# SCH_ALL-IN-ONE_2025-01-04.net
KiCad netlist of a schematic drawn in EasyEDA
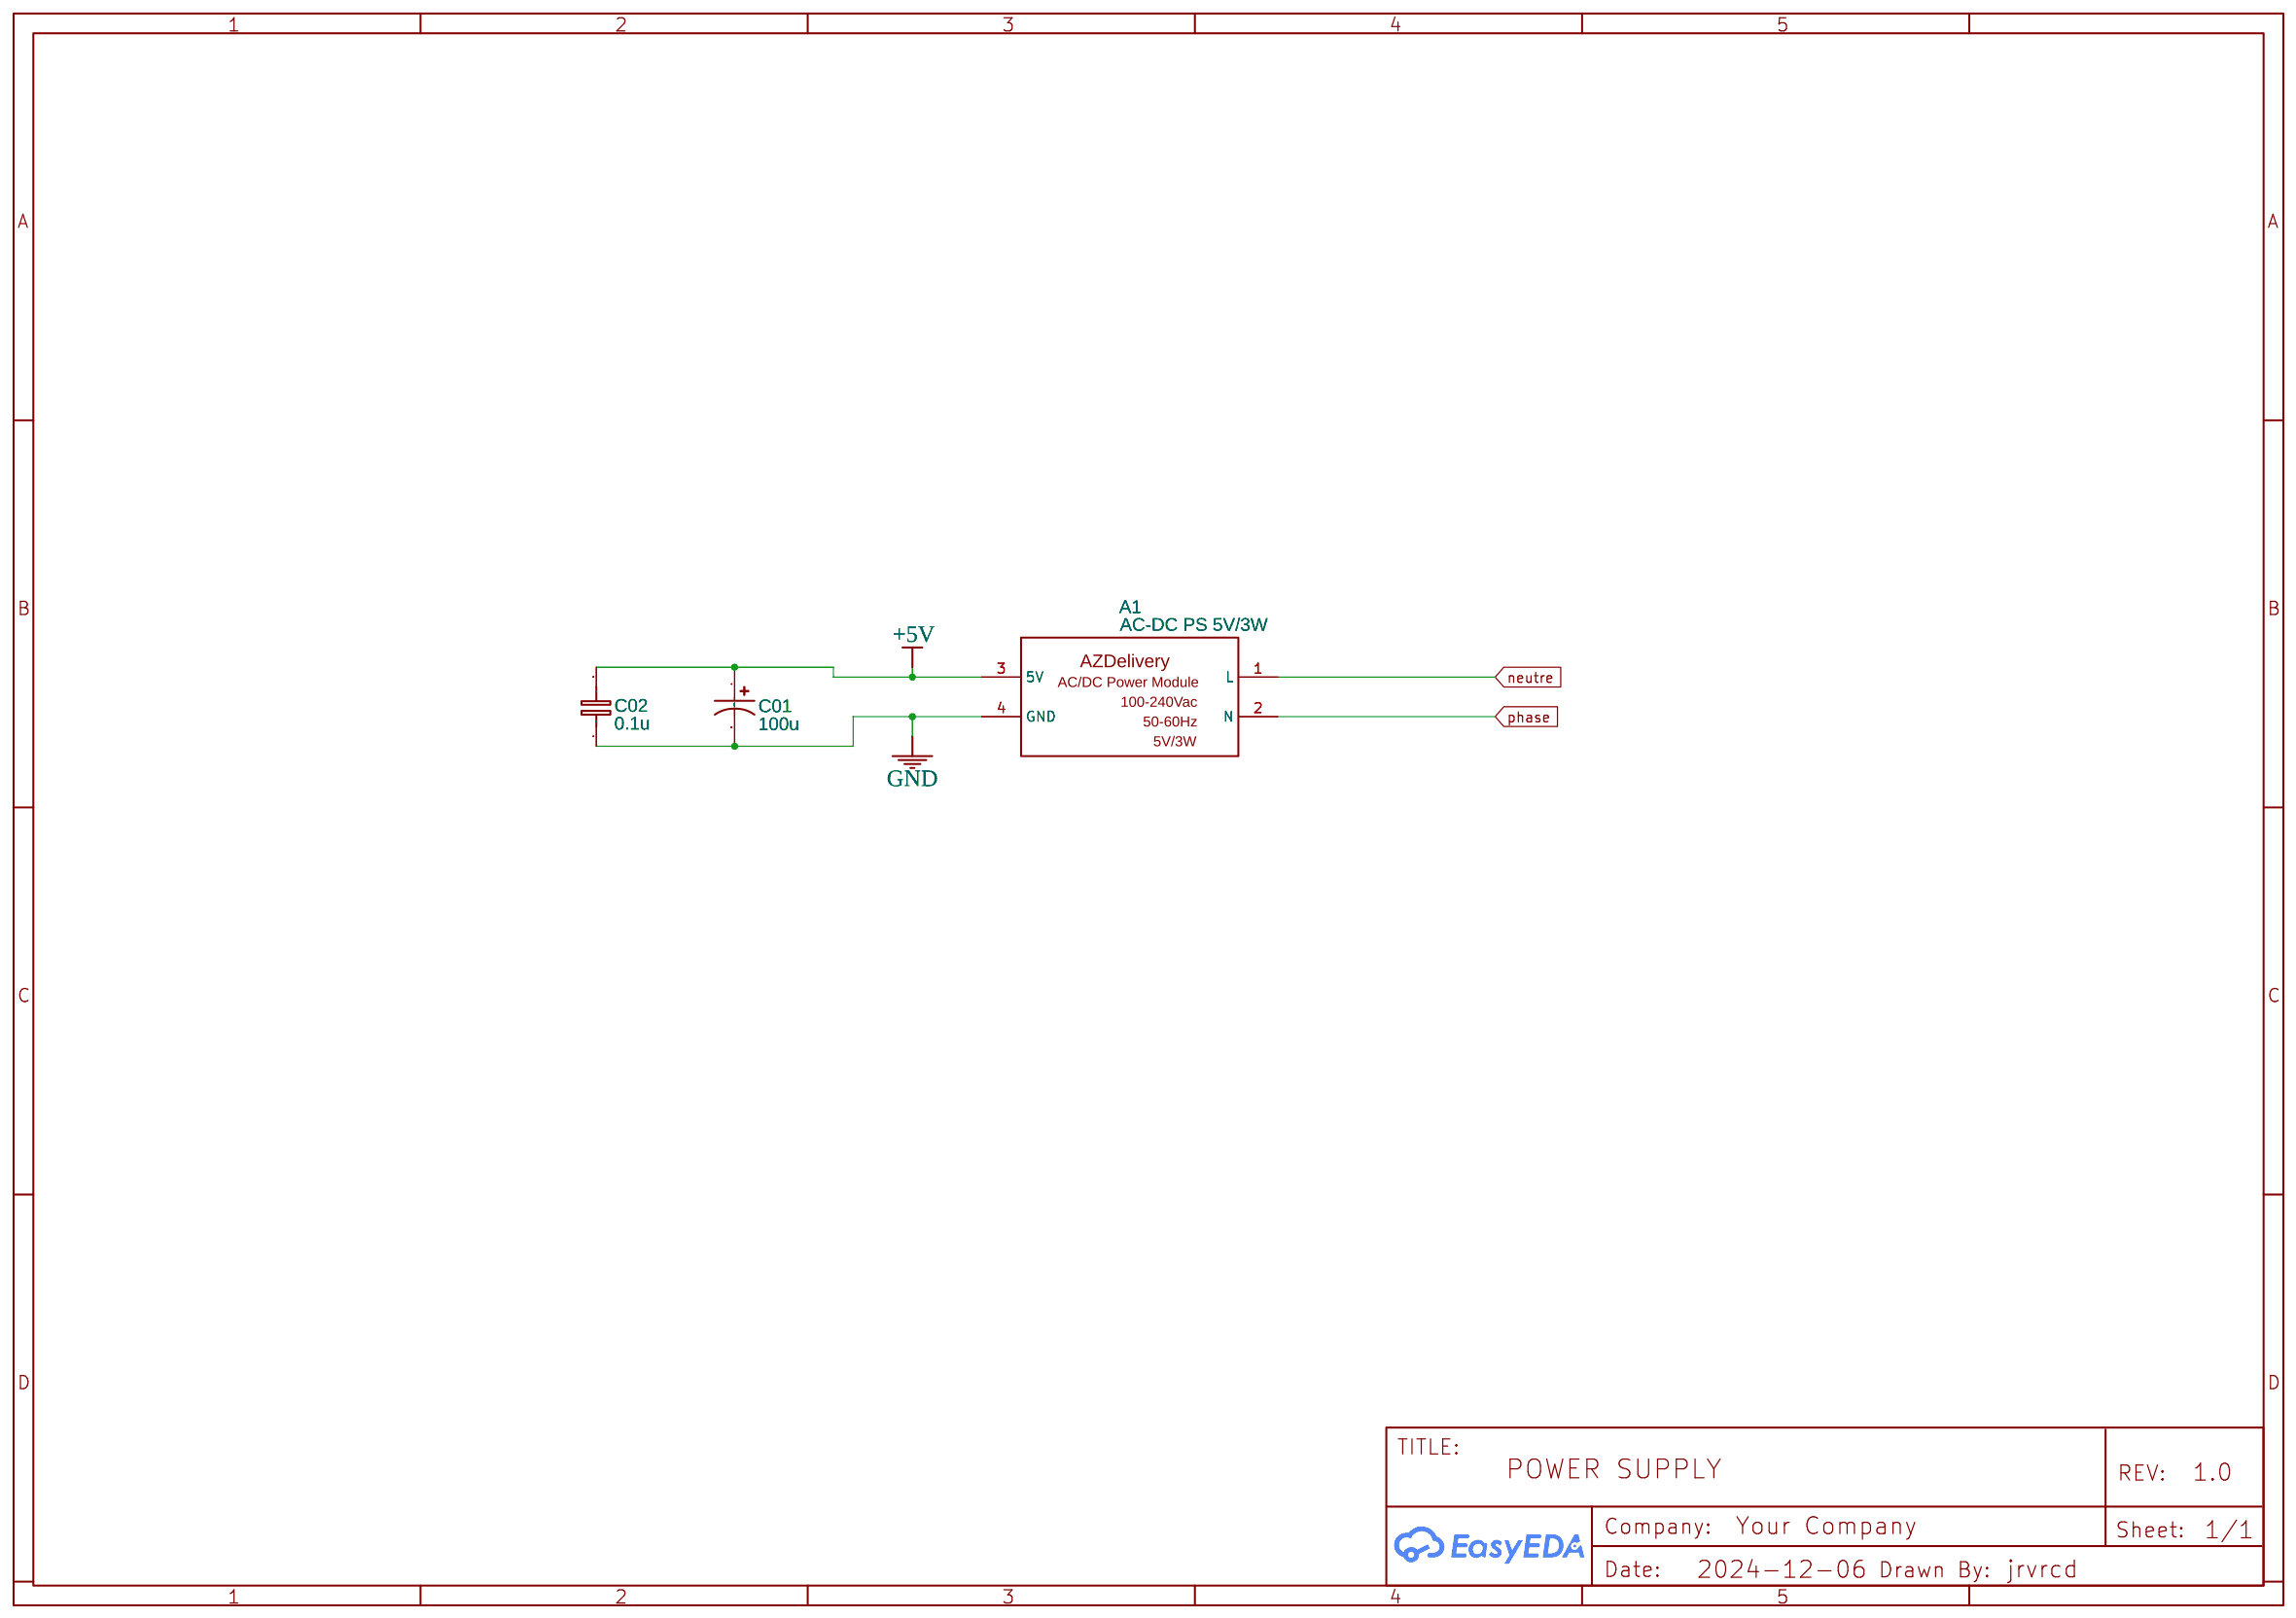
[diagram p0: power supply]
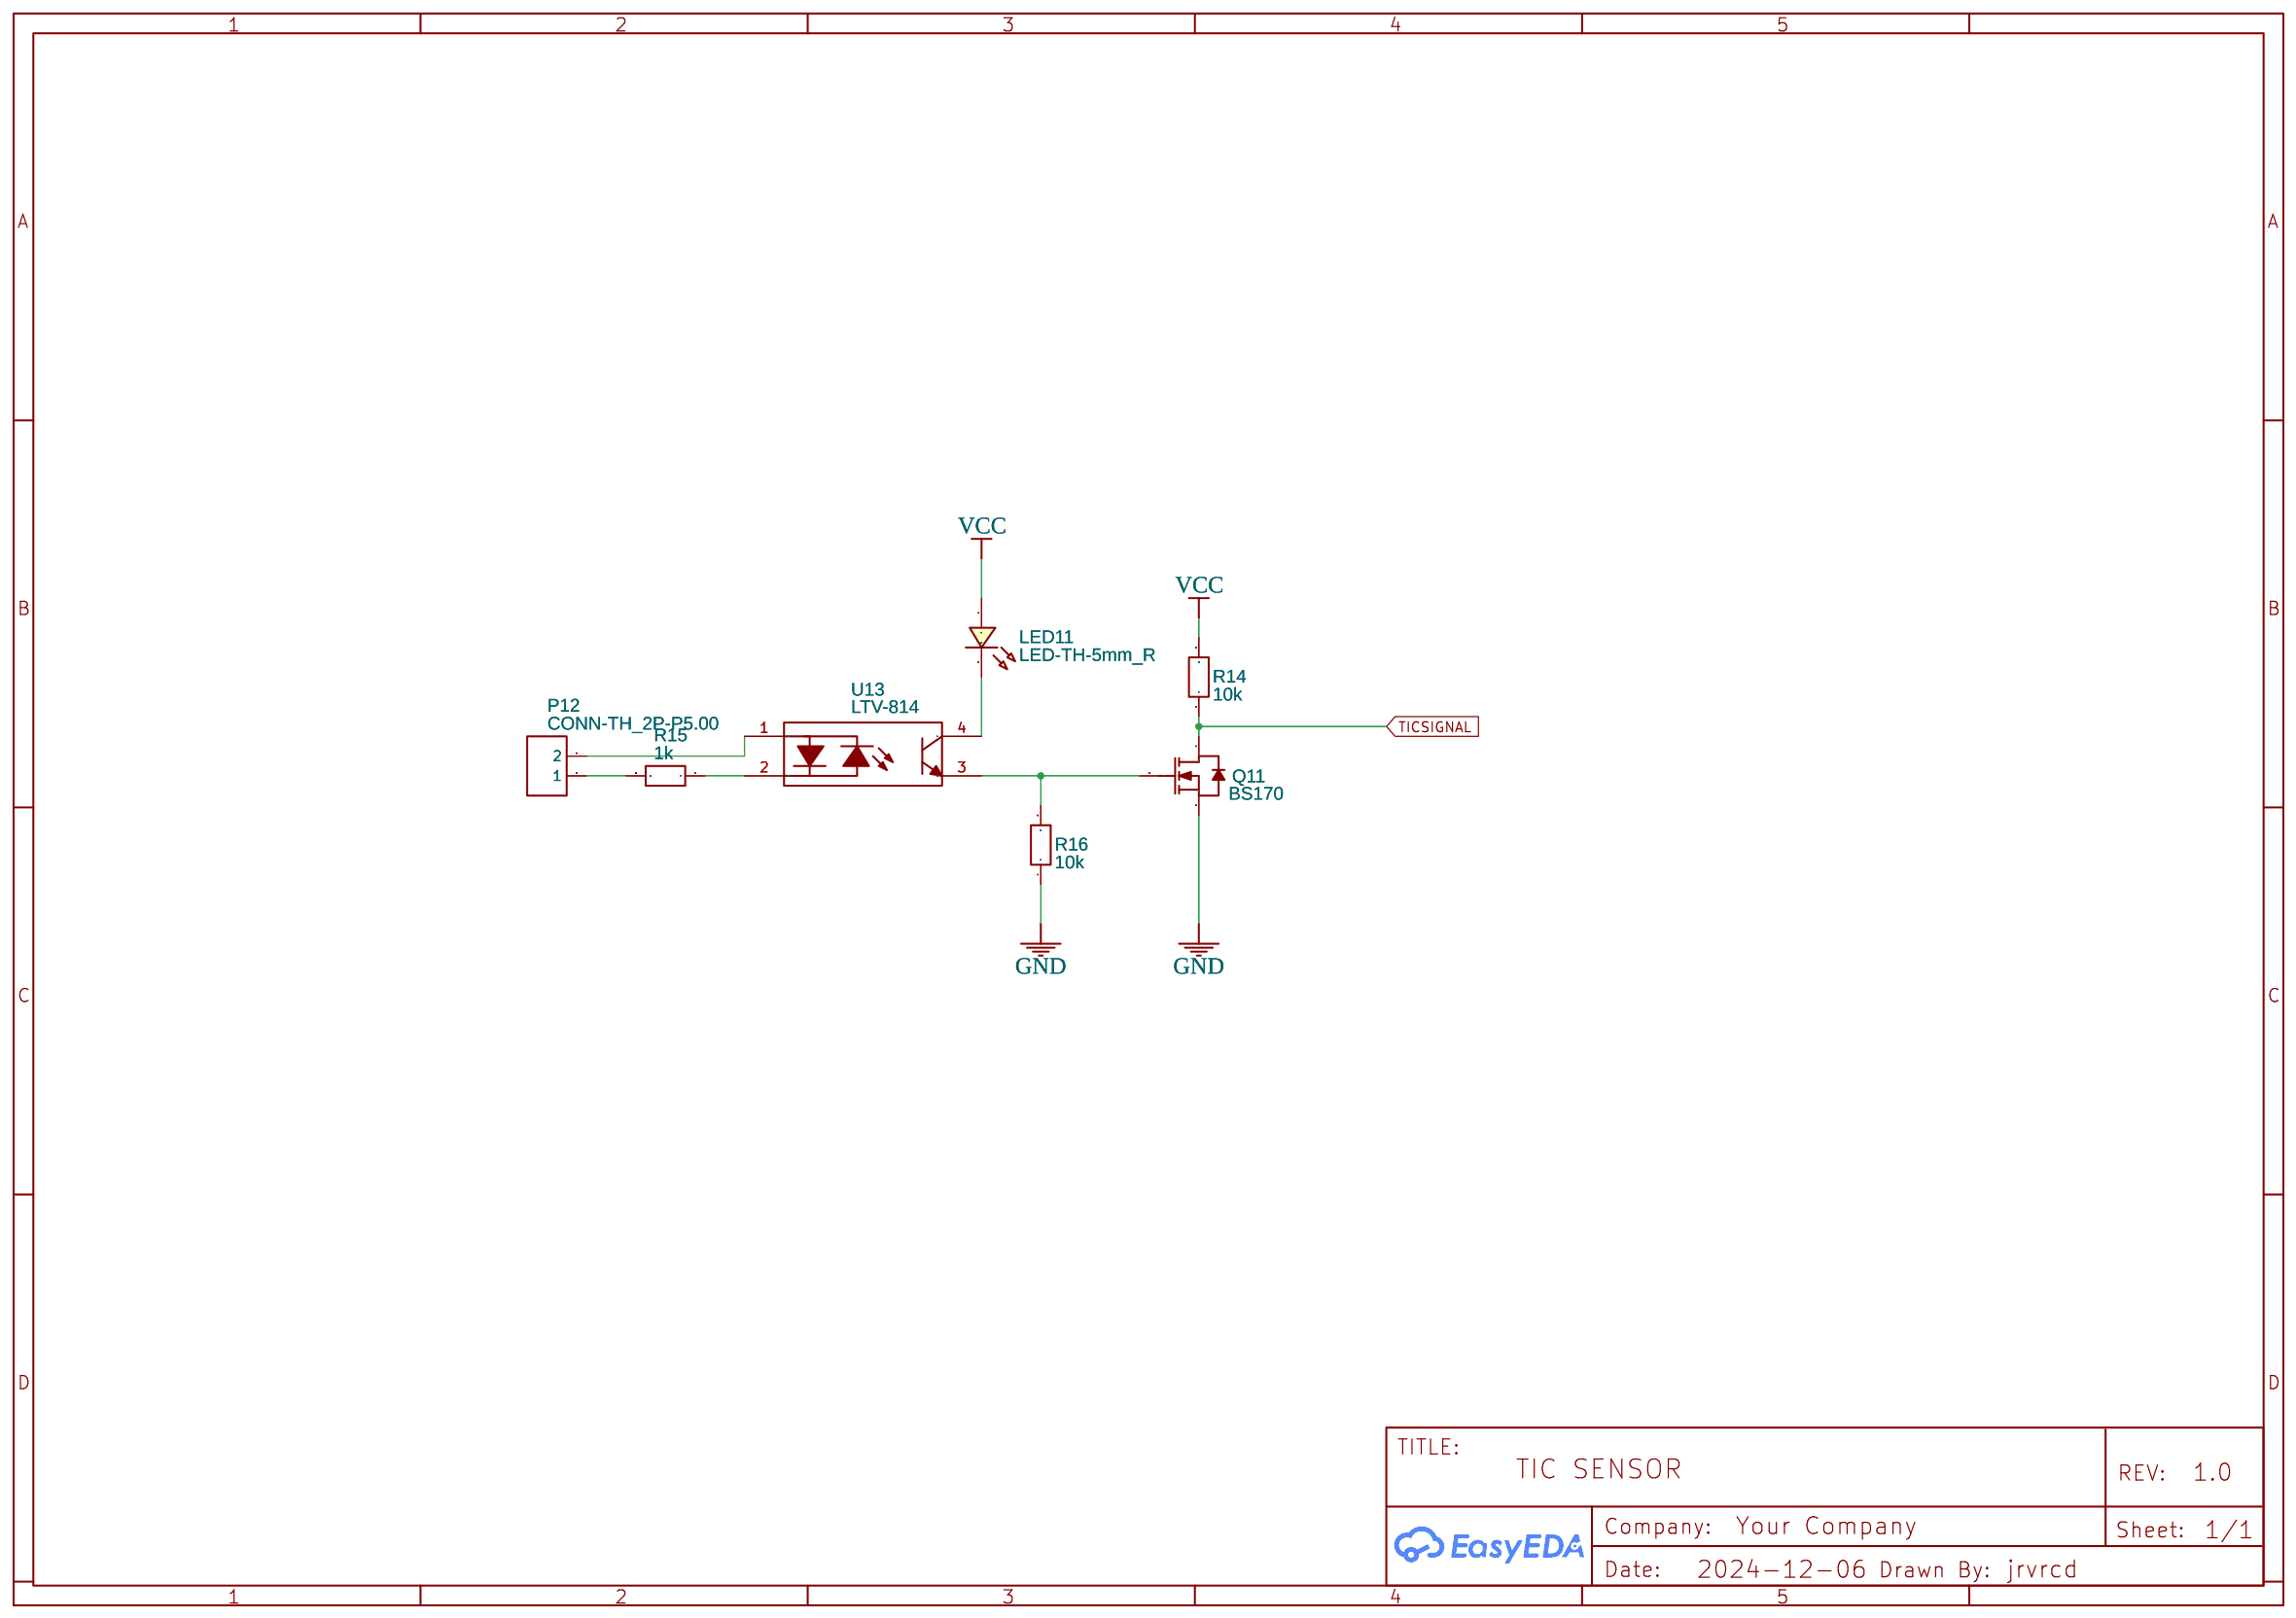
[diagram p1: TIC SENSOR]
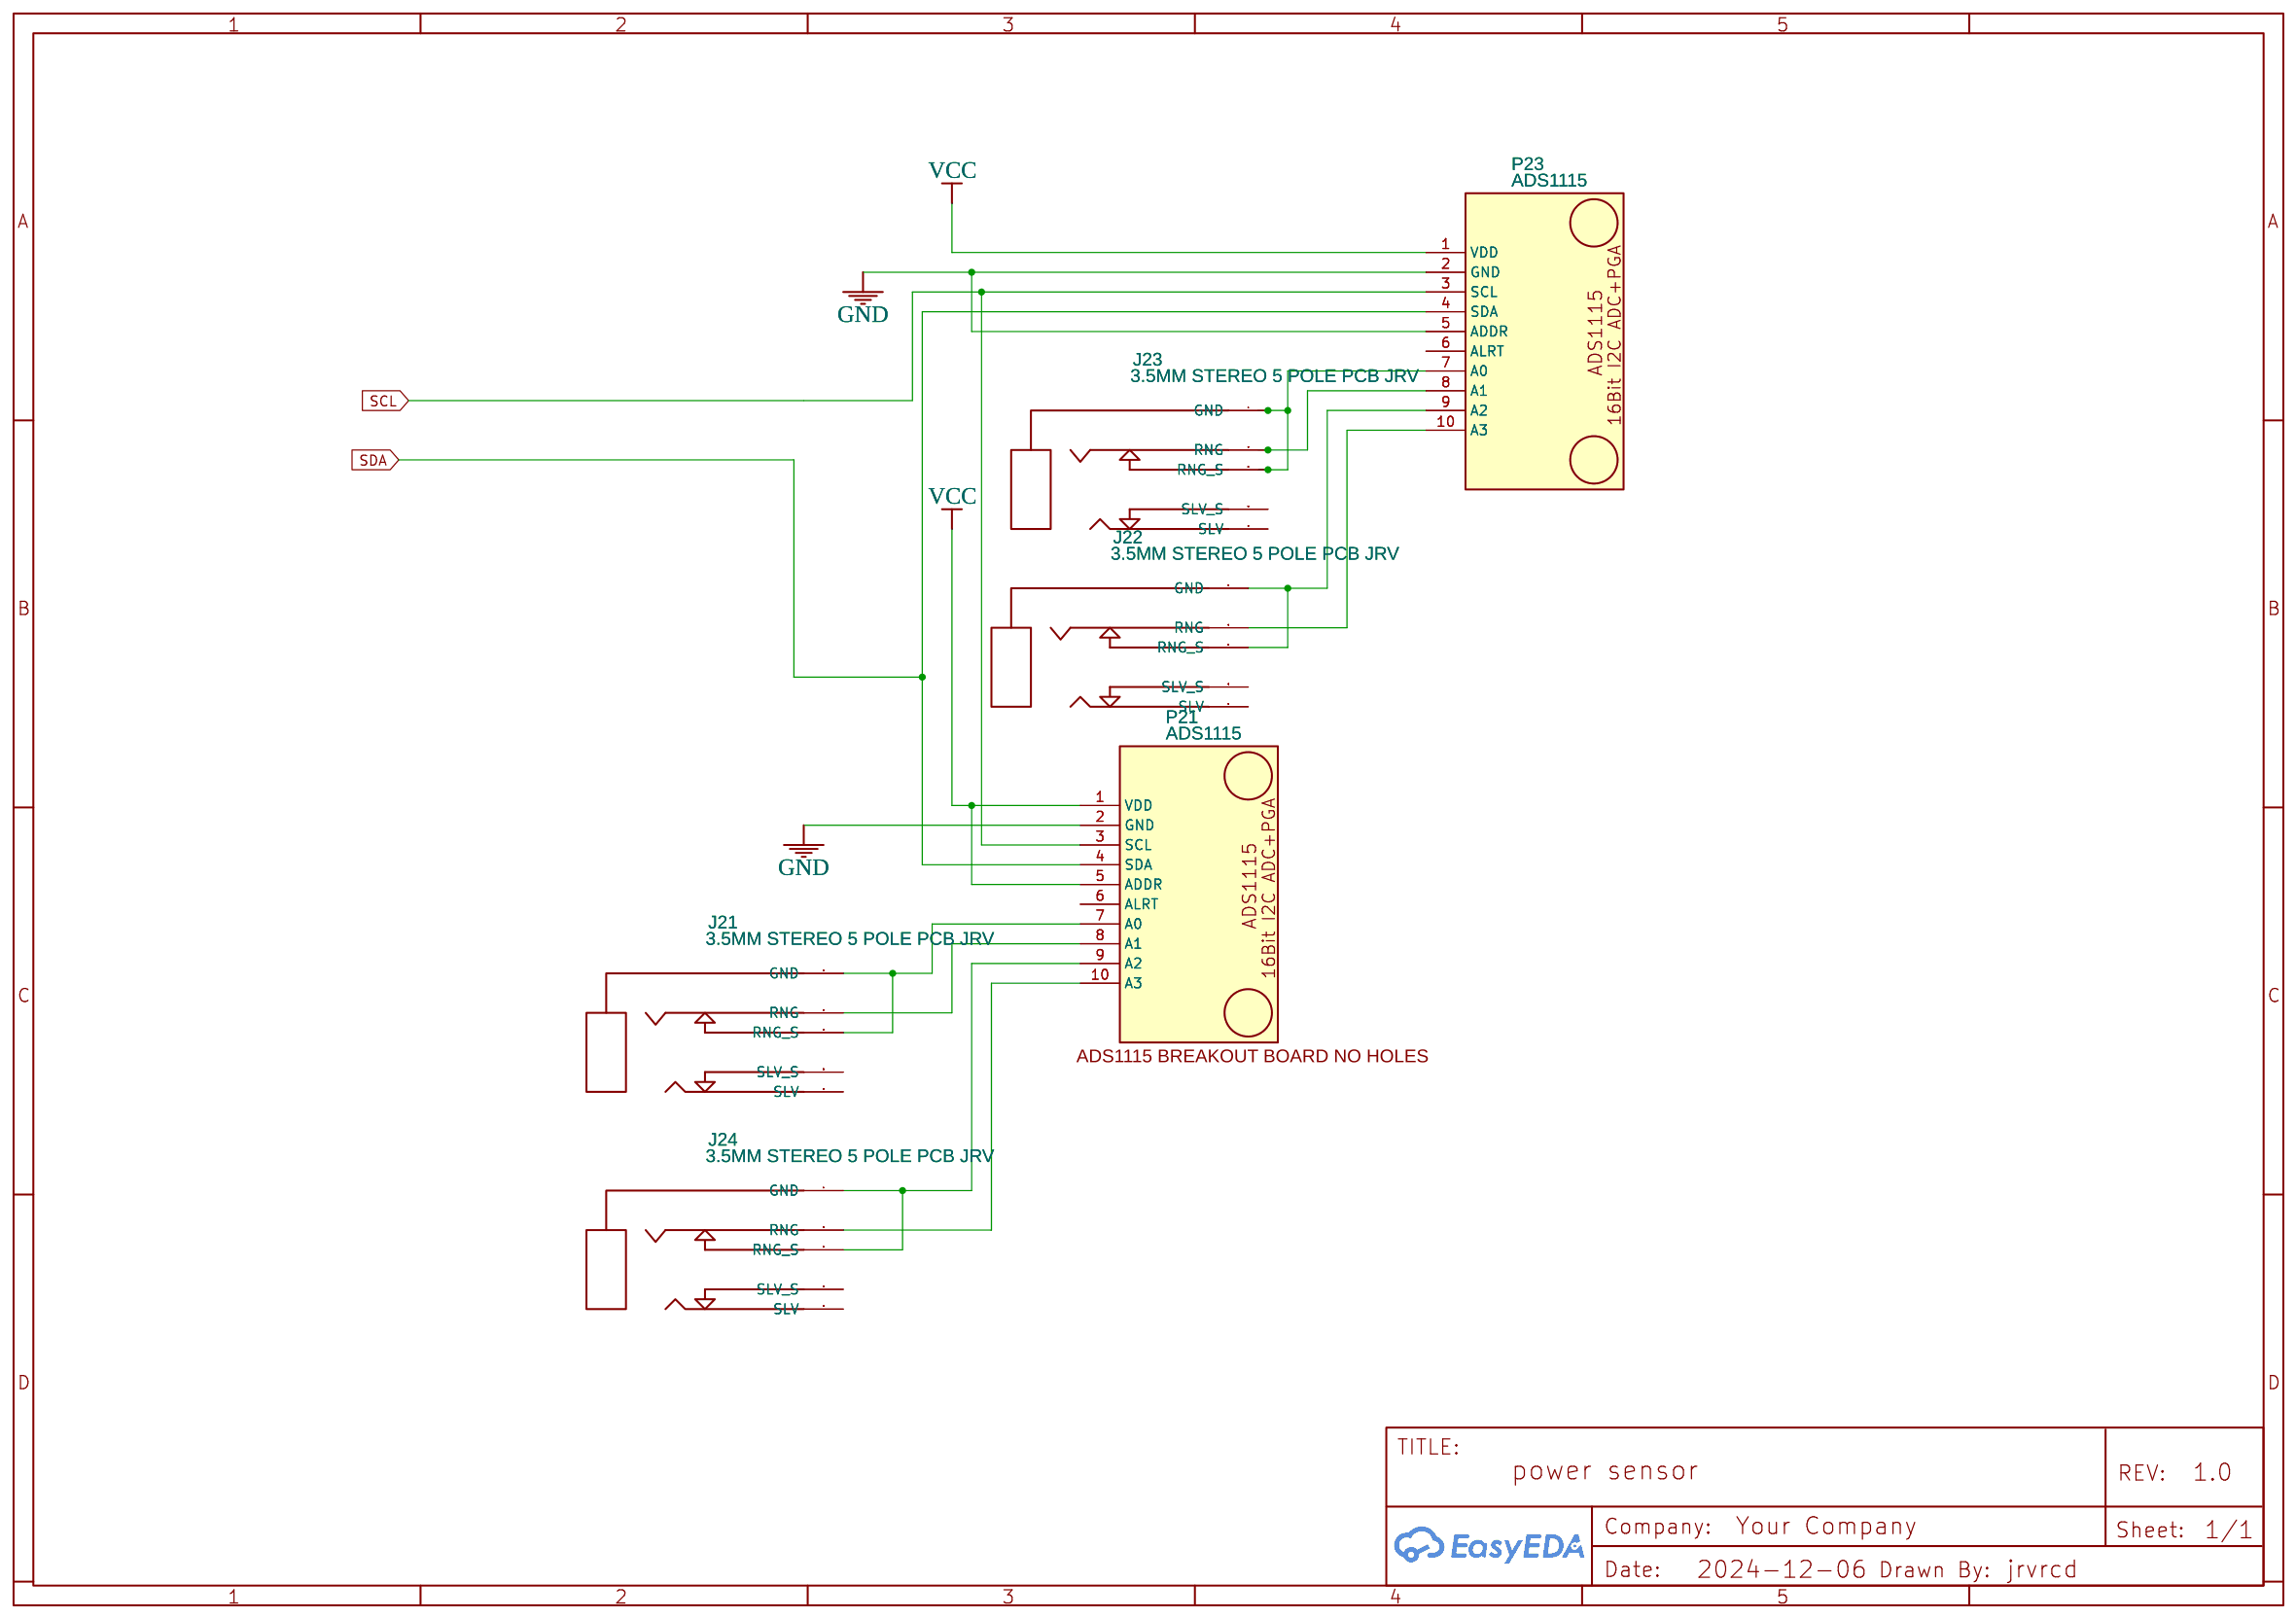
[diagram p2: POWER SENSOR]
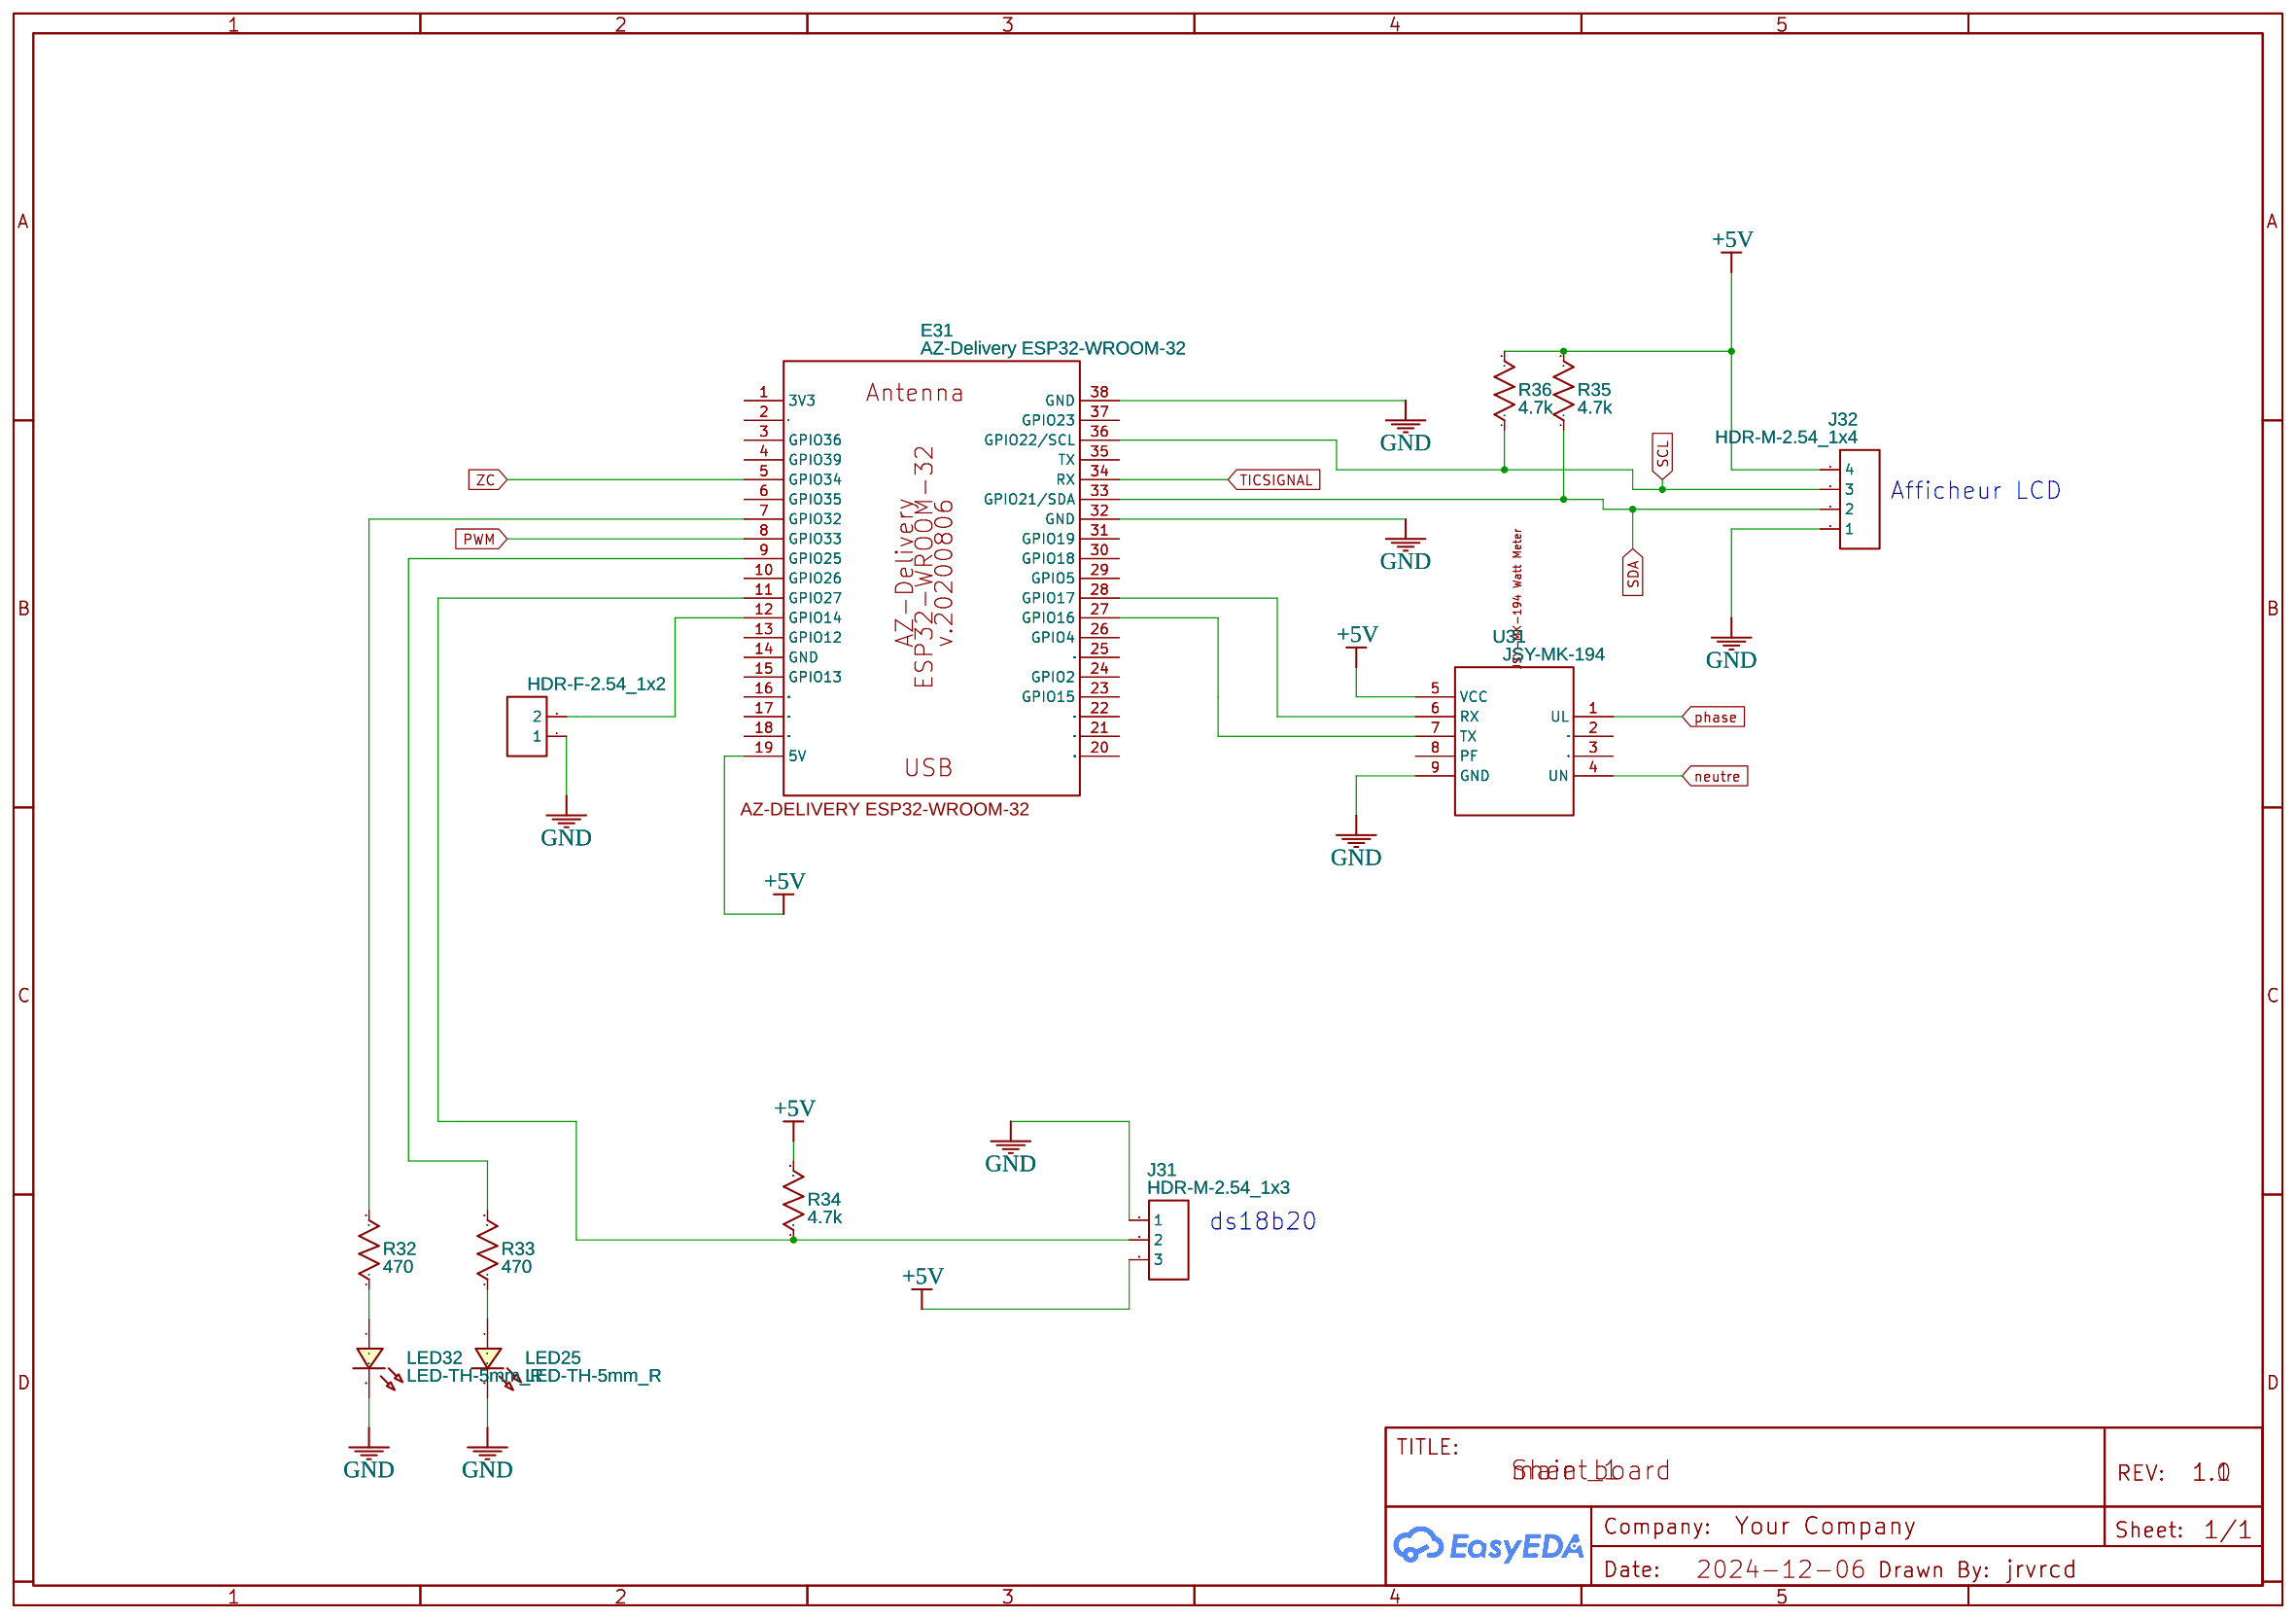
[diagram p3: main board]
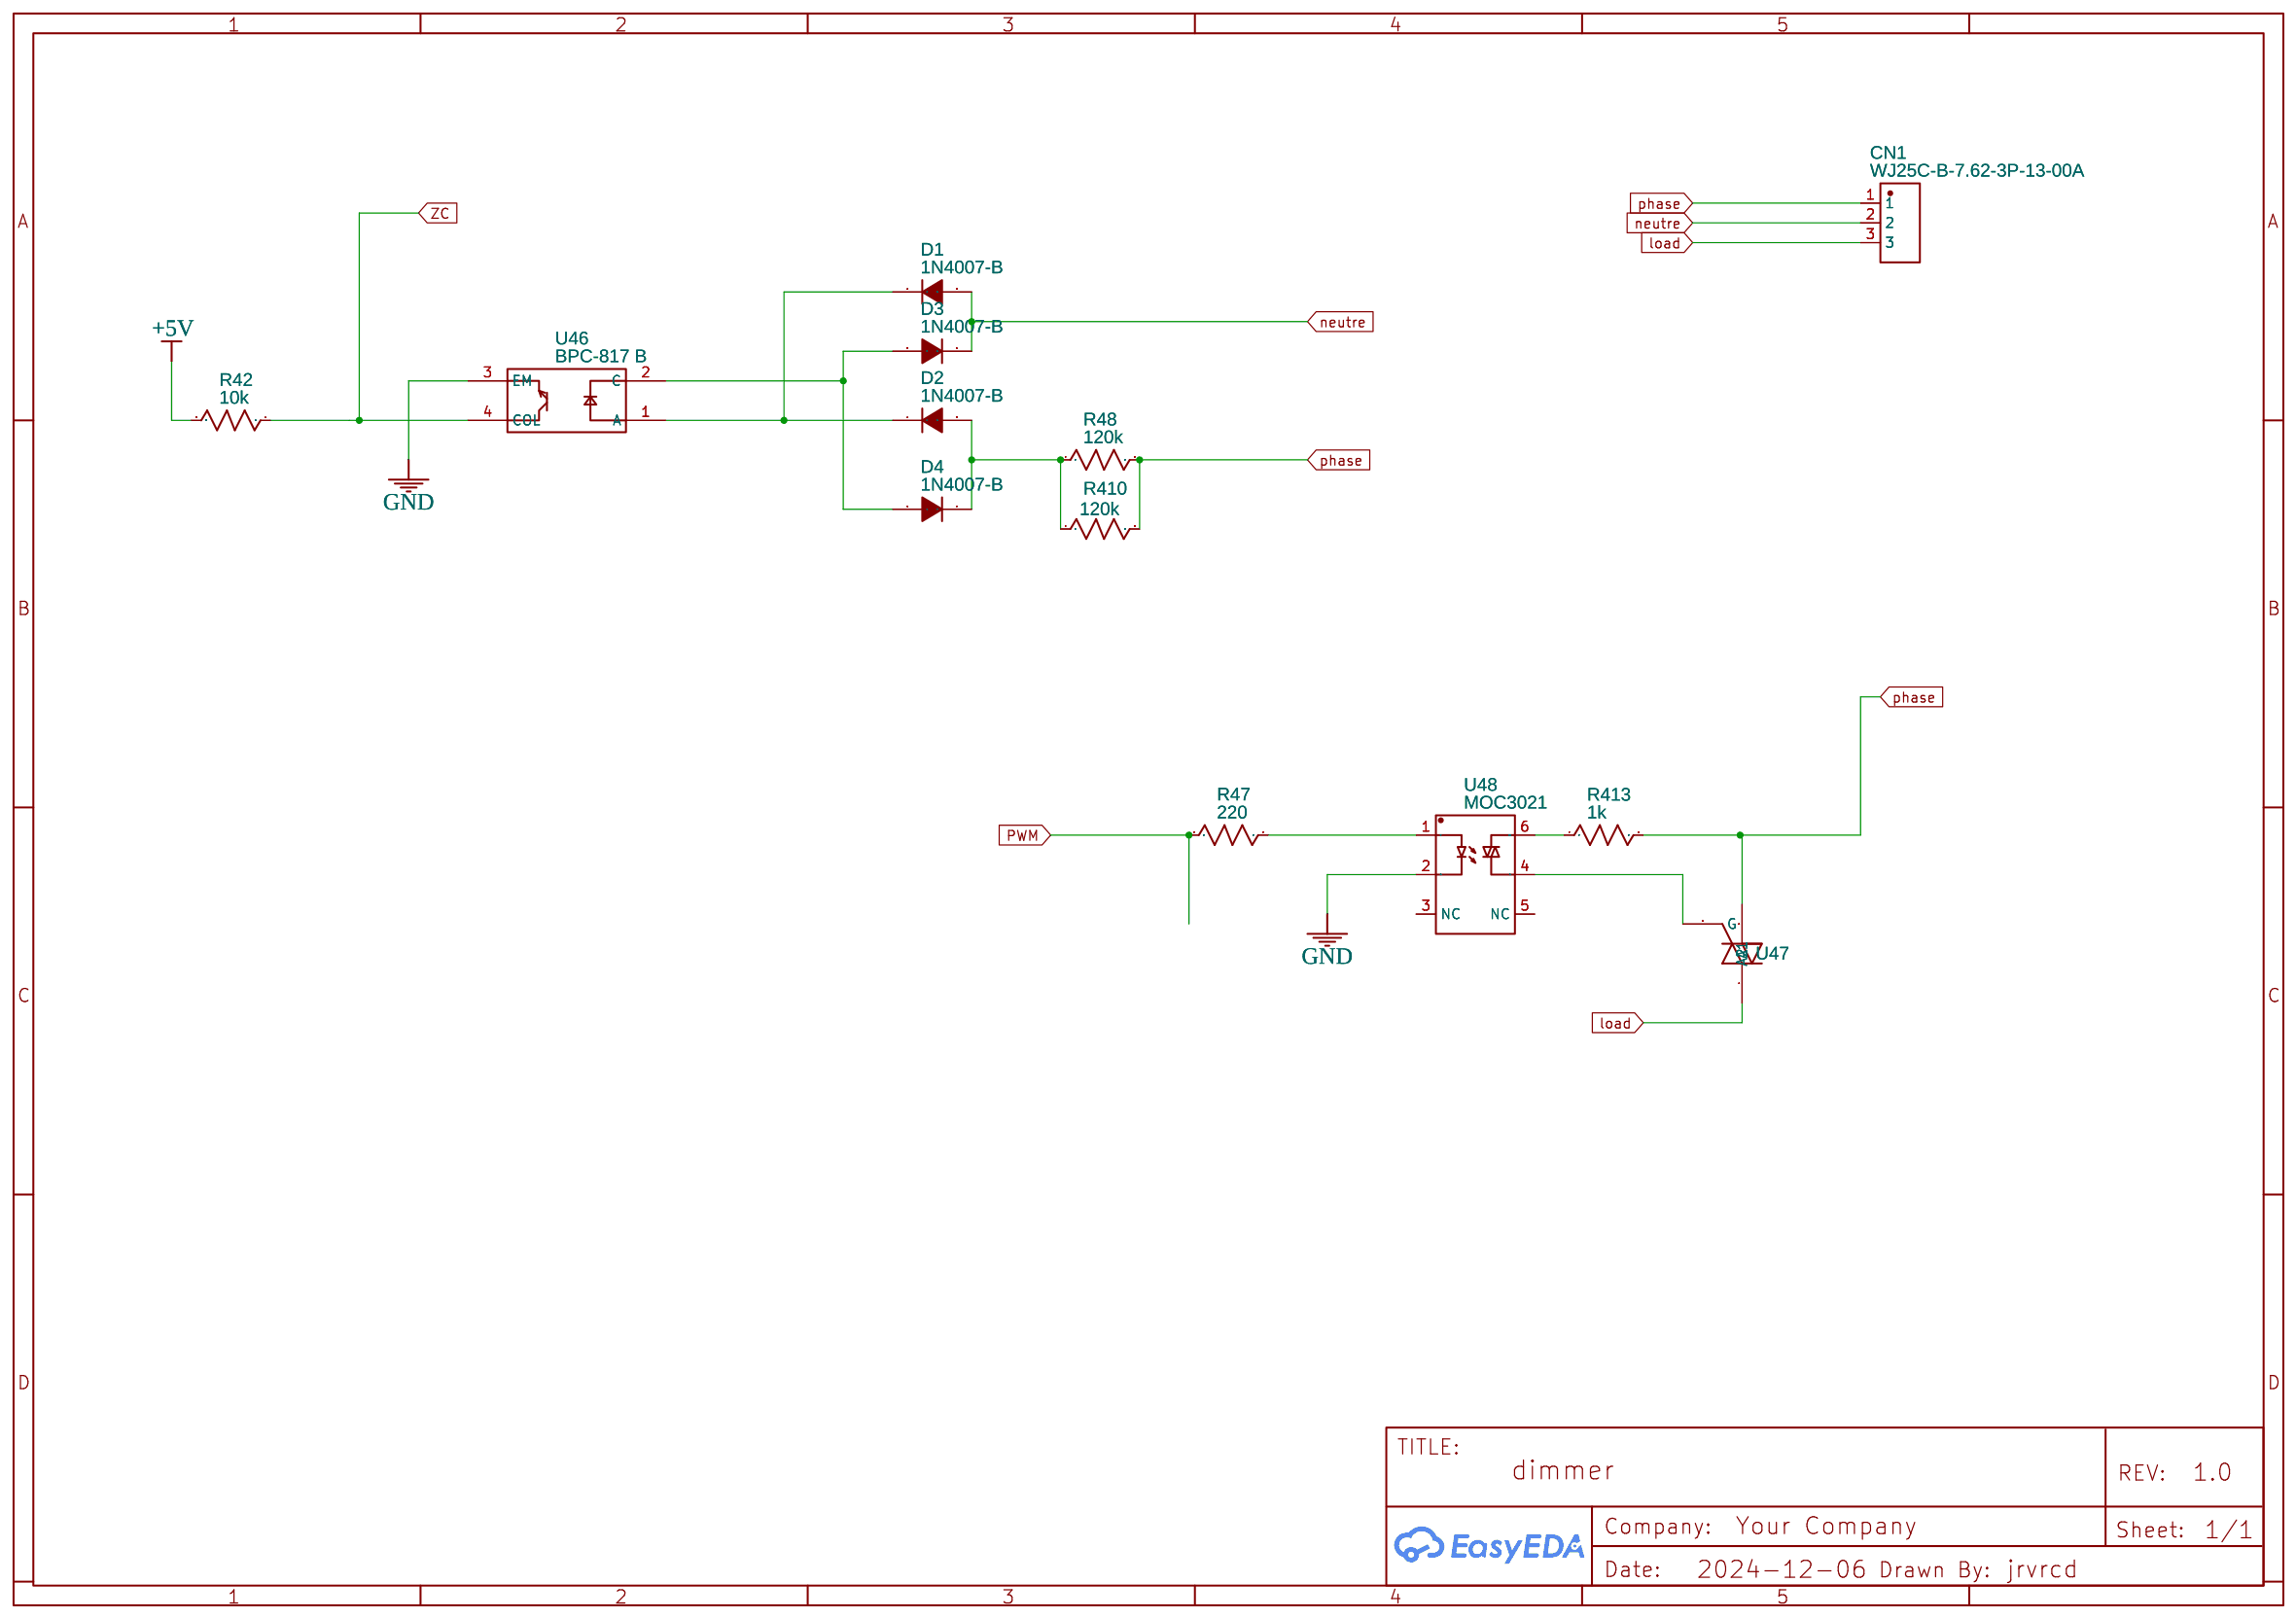
[diagram p4: dimmer]

(export (version "E")
  (design (tool "Eeschema 10.0.6"))
  (components
    (comp (ref "A1")
      (value "AC-DC PS 5V/3W")
      (fields (field (name "Manufacturer Part") "AC-05-3") (field (name "Manufacturer") "AZDelivery"))
      (libsource (lib "") (part "AC-DC PS 5V/3W"))
    )
    (comp (ref "C01") (value "100u") (libsource (lib "") (part "CE_TH_D3.0×F1.5_US")))
    (comp (ref "C02") (value "0.1u") (libsource (lib "") (part "C_RAD-0.3_EU")))
    (comp (ref "LED11")
      (value "LED-TH-5mm_R")
      (fields
        (field (name "Manufacturer Part") "333-2SURD/S530-A3")
        (field (name "Manufacturer") "EVERLIGHT(台湾亿光)")
      )
      (libsource (lib "") (part "LED-TH-5mm_R"))
    )
    (comp (ref "P12") (value "CONN-TH_2P-P5.00") (libsource (lib "") (part "CONN-TH_2P-P5.00")))
    (comp (ref "Q11")
      (value "BS170")
      (fields (field (name "Manufacturer") "FAIRCHILD"))
      (libsource (lib "") (part "BS170"))
    )
    (comp (ref "R14") (value "10k") (libsource (lib "") (part "R_AXIAL-0.3_EU")))
    (comp (ref "R15") (value "1k") (libsource (lib "") (part "R_AXIAL-0.3_EU_1")))
    (comp (ref "R16") (value "10k") (libsource (lib "") (part "R_AXIAL-0.3_EU")))
    (comp (ref "U13")
      (value "LTV-814")
      (fields (field (name "Manufacturer") "LITEON"))
      (libsource (lib "") (part "LTV-814"))
    )
    (comp (ref "J21")
      (value "3.5MM STEREO 5 POLE PCB JRV")
      (fields (field (name "Manufacturer Part") "913-1021") (field (name "Manufacturer") "RS-PRO"))
      (libsource (lib "") (part "3.5MM STEREO 5 POLE PCB JRV"))
    )
    (comp (ref "J22")
      (value "3.5MM STEREO 5 POLE PCB JRV")
      (fields (field (name "Manufacturer Part") "913-1021") (field (name "Manufacturer") "RS-PRO"))
      (libsource (lib "") (part "3.5MM STEREO 5 POLE PCB JRV"))
    )
    (comp (ref "J23")
      (value "3.5MM STEREO 5 POLE PCB JRV")
      (fields (field (name "Manufacturer Part") "913-1021") (field (name "Manufacturer") "RS-PRO"))
      (libsource (lib "") (part "3.5MM STEREO 5 POLE PCB JRV"))
    )
    (comp (ref "J24")
      (value "3.5MM STEREO 5 POLE PCB JRV")
      (fields (field (name "Manufacturer Part") "913-1021") (field (name "Manufacturer") "RS-PRO"))
      (libsource (lib "") (part "3.5MM STEREO 5 POLE PCB JRV"))
    )
    (comp (ref "P21") (value "ADS1115") (libsource (lib "") (part "ADS1115")))
    (comp (ref "P23") (value "ADS1115") (libsource (lib "") (part "ADS1115_1")))
    (comp (ref "E31")
      (value "AZ-Delivery ESP32-WROOM-32")
      (libsource (lib "") (part "AZ-Delivery ESP32-WROOM-32"))
    )
    (comp (ref "H1") (value "HDR-F-2.54_1x2") (libsource (lib "") (part "HDR-F-2.54_1x2")))
    (comp (ref "J31") (value "HDR-M-2.54_1x3") (libsource (lib "") (part "HDR-M-2.54_1x3")))
    (comp (ref "J32") (value "HDR-M-2.54_1x4") (libsource (lib "") (part "HDR-M-2.54_1x4")))
    (comp (ref "LED25")
      (value "LED-TH-5mm_R")
      (fields
        (field (name "Manufacturer Part") "333-2SURD/S530-A3")
        (field (name "Manufacturer") "EVERLIGHT(台湾亿光)")
      )
      (libsource (lib "") (part "LED-TH-5mm_R"))
    )
    (comp (ref "LED32")
      (value "LED-TH-5mm_R")
      (fields
        (field (name "Manufacturer Part") "333-2SURD/S530-A3")
        (field (name "Manufacturer") "EVERLIGHT(台湾亿光)")
      )
      (libsource (lib "") (part "LED-TH-5mm_R"))
    )
    (comp (ref "R32") (value "470") (libsource (lib "") (part "R_AXIAL-0.3_US")))
    (comp (ref "R33") (value "470") (libsource (lib "") (part "R_AXIAL-0.3_US")))
    (comp (ref "R34") (value "4.7k") (libsource (lib "") (part "R_AXIAL-0.3_US")))
    (comp (ref "R35") (value "4.7k") (libsource (lib "") (part "R_AXIAL-0.3_US")))
    (comp (ref "R36") (value "4.7k") (libsource (lib "") (part "R_AXIAL-0.3_US")))
    (comp (ref "U31")
      (value "JSY-MK-194")
      (fields (field (name "Manufacturer") "PEJ"))
      (libsource (lib "") (part "JSY-MK-194"))
    )
    (comp (ref "CN1")
      (value "WJ25C-B-7.62-3P-13-00A")
      (fields
        (field (name "Manufacturer Part") "WJ25C-B-7.62-3P")
        (field (name "Manufacturer") "KANGNEX(康奈克斯电气)")
      )
      (libsource (lib "") (part "WJ25C-B-7.62-3P-13-00A"))
    )
    (comp (ref "D1")
      (value "1N4007-B")
      (fields (field (name "Manufacturer") "Diodes Incorporated"))
      (libsource (lib "") (part "1N4007-B"))
    )
    (comp (ref "D2")
      (value "1N4007-B")
      (fields (field (name "Manufacturer") "Diodes Incorporated"))
      (libsource (lib "") (part "1N4007-B"))
    )
    (comp (ref "D3")
      (value "1N4007-B")
      (fields (field (name "Manufacturer") "Diodes Incorporated"))
      (libsource (lib "") (part "1N4007-B_1"))
    )
    (comp (ref "D4")
      (value "1N4007-B")
      (fields (field (name "Manufacturer") "Diodes Incorporated"))
      (libsource (lib "") (part "1N4007-B_1"))
    )
    (comp (ref "R42") (value "10k") (libsource (lib "") (part "R_AXIAL-0.3_US_1")))
    (comp (ref "R47") (value "220") (libsource (lib "") (part "R_AXIAL-0.3_US_1")))
    (comp (ref "R48") (value "120k") (libsource (lib "") (part "R_AXIAL-0.3_US")))
    (comp (ref "R410") (value "120k") (libsource (lib "") (part "R_AXIAL-0.3_US")))
    (comp (ref "R413") (value "1k") (libsource (lib "") (part "R_AXIAL-0.3_US")))
    (comp (ref "U46")
      (value "BPC-817 B")
      (fields (field (name "Manufacturer Part") "BPC-817") (field (name "Manufacturer") "BrtLed(佰鸿)"))
      (libsource (lib "") (part "BPC-817 B"))
    )
    (comp (ref "U47") (value "NO") (libsource (lib "") (part "BTA41")))
    (comp (ref "U48")
      (value "MOC3021")
      (fields (field (name "Manufacturer") "Lite-On"))
      (libsource (lib "") (part "MOC3021"))
    )
  )
  (nets
    (net (code "1") (name "+5V") (class "Default")
      (node (ref "A1") (pin "3") (pinfunction "5V_3") (pintype "unspecified"))
      (node (ref "C01") (pin "1") (pinfunction "1_1") (pintype "unspecified"))
      (node (ref "C02") (pin "2") (pinfunction "2_2") (pintype "unspecified"))
      (node (ref "E31") (pin "19") (pinfunction "5V_19") (pintype "unspecified"))
      (node (ref "J31") (pin "3") (pinfunction "3_3") (pintype "input"))
      (node (ref "J32") (pin "4") (pinfunction "4_4") (pintype "unspecified"))
      (node (ref "R34") (pin "2") (pinfunction "2_2") (pintype "unspecified"))
      (node (ref "R35") (pin "2") (pinfunction "2_2") (pintype "unspecified"))
      (node (ref "R36") (pin "2") (pinfunction "2_2") (pintype "unspecified"))
      (node (ref "R42") (pin "2") (pinfunction "2_2") (pintype "unspecified"))
      (node (ref "U31") (pin "5") (pinfunction "VCC_5") (pintype "unspecified"))
    )
    (net (code "2") (name "GND") (class "Default")
      (node (ref "A1") (pin "4") (pinfunction "GND_4") (pintype "unspecified"))
      (node (ref "C01") (pin "2") (pinfunction "2_2") (pintype "unspecified"))
      (node (ref "C02") (pin "1") (pinfunction "1_1") (pintype "unspecified"))
      (node (ref "E31") (pin "32") (pinfunction "GND_32") (pintype "unspecified"))
      (node (ref "E31") (pin "38") (pinfunction "GND_38") (pintype "unspecified"))
      (node (ref "H1") (pin "1") (pinfunction "1_1") (pintype "input"))
      (node (ref "J31") (pin "1") (pinfunction "1_1") (pintype "input"))
      (node (ref "J32") (pin "1") (pinfunction "1_1") (pintype "unspecified"))
      (node (ref "LED25") (pin "2") (pinfunction "2_2") (pintype "unspecified"))
      (node (ref "LED32") (pin "2") (pinfunction "2_2") (pintype "unspecified"))
      (node (ref "P21") (pin "2") (pinfunction "GND_2") (pintype "passive"))
      (node (ref "P23") (pin "2") (pinfunction "GND_2") (pintype "passive"))
      (node (ref "P23") (pin "5") (pinfunction "ADDR_5") (pintype "passive"))
      (node (ref "Q11") (pin "3") (pinfunction "S_3") (pintype "unspecified"))
      (node (ref "R16") (pin "1") (pinfunction "1_1") (pintype "unspecified"))
      (node (ref "U31") (pin "9") (pinfunction "GND_9") (pintype "unspecified"))
      (node (ref "U46") (pin "3") (pinfunction "EM_3") (pintype "unspecified"))
      (node (ref "U48") (pin "2") (pinfunction "2_2") (pintype "unspecified"))
    )
    (net (code "3") (name "Net-(D1-K)") (class "Default")
      (node (ref "D1") (pin "1") (pinfunction "K_1") (pintype "unspecified"))
      (node (ref "D2") (pin "1") (pinfunction "K_1") (pintype "unspecified"))
      (node (ref "U46") (pin "1") (pinfunction "A_1") (pintype "unspecified"))
    )
    (net (code "4") (name "Net-(D2-A)") (class "Default")
      (node (ref "D2") (pin "2") (pinfunction "A_2") (pintype "unspecified"))
      (node (ref "D4") (pin "1") (pinfunction "K_1") (pintype "unspecified"))
      (node (ref "R410") (pin "1") (pinfunction "1_1") (pintype "unspecified"))
      (node (ref "R48") (pin "1") (pinfunction "1_1") (pintype "unspecified"))
    )
    (net (code "5") (name "Net-(D3-A)") (class "Default")
      (node (ref "D3") (pin "2") (pinfunction "A_2") (pintype "unspecified"))
      (node (ref "D4") (pin "2") (pinfunction "A_2") (pintype "unspecified"))
      (node (ref "U46") (pin "2") (pinfunction "C_2") (pintype "unspecified"))
    )
    (net (code "6") (name "Net-(E31-GPIO14)") (class "Default")
      (node (ref "E31") (pin "12") (pinfunction "GPIO14_12") (pintype "unspecified"))
      (node (ref "H1") (pin "2") (pinfunction "2_2") (pintype "input"))
    )
    (net (code "7") (name "Net-(E31-GPIO16)") (class "Default")
      (node (ref "E31") (pin "27") (pinfunction "GPIO16_27") (pintype "unspecified"))
      (node (ref "U31") (pin "7") (pinfunction "TX_7") (pintype "unspecified"))
    )
    (net (code "8") (name "Net-(E31-GPIO17)") (class "Default")
      (node (ref "E31") (pin "28") (pinfunction "GPIO17_28") (pintype "unspecified"))
      (node (ref "U31") (pin "6") (pinfunction "RX_6") (pintype "unspecified"))
    )
    (net (code "9") (name "Net-(E31-GPIO25)") (class "Default")
      (node (ref "E31") (pin "9") (pinfunction "GPIO25_9") (pintype "unspecified"))
      (node (ref "R33") (pin "2") (pinfunction "2_2") (pintype "unspecified"))
    )
    (net (code "10") (name "Net-(E31-GPIO27)") (class "Default")
      (node (ref "E31") (pin "11") (pinfunction "GPIO27_11") (pintype "unspecified"))
      (node (ref "J31") (pin "2") (pinfunction "2_2") (pintype "input"))
      (node (ref "R34") (pin "1") (pinfunction "1_1") (pintype "unspecified"))
    )
    (net (code "11") (name "Net-(E31-GPIO32)") (class "Default")
      (node (ref "E31") (pin "7") (pinfunction "GPIO32_7") (pintype "unspecified"))
      (node (ref "R32") (pin "2") (pinfunction "2_2") (pintype "unspecified"))
    )
    (net (code "12") (name "Net-(J21-GND)") (class "Default")
      (node (ref "J21") (pin "1") (pinfunction "GND_1") (pintype "unspecified"))
      (node (ref "J21") (pin "11") (pinfunction "RNG_S_11") (pintype "unspecified"))
      (node (ref "P21") (pin "7") (pinfunction "A0_7") (pintype "unspecified"))
    )
    (net (code "13") (name "Net-(J21-RNG)") (class "Default")
      (node (ref "J21") (pin "3") (pinfunction "RNG_3") (pintype "unspecified"))
      (node (ref "P21") (pin "8") (pinfunction "A1_8") (pintype "unspecified"))
    )
    (net (code "14") (name "Net-(J22-GND)") (class "Default")
      (node (ref "J22") (pin "1") (pinfunction "GND_1") (pintype "unspecified"))
      (node (ref "J22") (pin "11") (pinfunction "RNG_S_11") (pintype "unspecified"))
      (node (ref "P23") (pin "9") (pinfunction "A2_9") (pintype "unspecified"))
    )
    (net (code "15") (name "Net-(J22-RNG)") (class "Default")
      (node (ref "J22") (pin "3") (pinfunction "RNG_3") (pintype "unspecified"))
      (node (ref "P23") (pin "10") (pinfunction "A3_10") (pintype "unspecified"))
    )
    (net (code "16") (name "Net-(J23-GND)") (class "Default")
      (node (ref "J23") (pin "1") (pinfunction "GND_1") (pintype "unspecified"))
      (node (ref "J23") (pin "11") (pinfunction "RNG_S_11") (pintype "unspecified"))
      (node (ref "P23") (pin "7") (pinfunction "A0_7") (pintype "unspecified"))
    )
    (net (code "17") (name "Net-(J23-RNG)") (class "Default")
      (node (ref "J23") (pin "3") (pinfunction "RNG_3") (pintype "unspecified"))
      (node (ref "P23") (pin "8") (pinfunction "A1_8") (pintype "unspecified"))
    )
    (net (code "18") (name "Net-(J24-GND)") (class "Default")
      (node (ref "J24") (pin "1") (pinfunction "GND_1") (pintype "unspecified"))
      (node (ref "J24") (pin "11") (pinfunction "RNG_S_11") (pintype "unspecified"))
      (node (ref "P21") (pin "9") (pinfunction "A2_9") (pintype "unspecified"))
    )
    (net (code "19") (name "Net-(J24-RNG)") (class "Default")
      (node (ref "J24") (pin "3") (pinfunction "RNG_3") (pintype "unspecified"))
      (node (ref "P21") (pin "10") (pinfunction "A3_10") (pintype "unspecified"))
    )
    (net (code "20") (name "Net-(LED11-Pad2)") (class "Default")
      (node (ref "LED11") (pin "2") (pinfunction "2_2") (pintype "unspecified"))
      (node (ref "U13") (pin "4") (pinfunction "4_4") (pintype "unspecified"))
    )
    (net (code "21") (name "Net-(LED25-Pad1)") (class "Default")
      (node (ref "LED25") (pin "1") (pinfunction "1_1") (pintype "unspecified"))
      (node (ref "R33") (pin "1") (pinfunction "1_1") (pintype "unspecified"))
    )
    (net (code "22") (name "Net-(LED32-Pad1)") (class "Default")
      (node (ref "LED32") (pin "1") (pinfunction "1_1") (pintype "unspecified"))
      (node (ref "R32") (pin "1") (pinfunction "1_1") (pintype "unspecified"))
    )
    (net (code "23") (name "Net-(P12-Pad1)") (class "Default")
      (node (ref "P12") (pin "1") (pinfunction "1_1") (pintype "unspecified"))
      (node (ref "R15") (pin "2") (pinfunction "2_2") (pintype "unspecified"))
    )
    (net (code "24") (name "Net-(P12-Pad2)") (class "Default")
      (node (ref "P12") (pin "2") (pinfunction "2_2") (pintype "unspecified"))
      (node (ref "U13") (pin "1") (pinfunction "1_1") (pintype "unspecified"))
    )
    (net (code "25") (name "Net-(Q11-G)") (class "Default")
      (node (ref "Q11") (pin "2") (pinfunction "G_2") (pintype "unspecified"))
      (node (ref "R16") (pin "2") (pinfunction "2_2") (pintype "unspecified"))
      (node (ref "U13") (pin "3") (pinfunction "3_3") (pintype "unspecified"))
    )
    (net (code "26") (name "Net-(R15-Pad1)") (class "Default")
      (node (ref "R15") (pin "1") (pinfunction "1_1") (pintype "unspecified"))
      (node (ref "U13") (pin "2") (pinfunction "2_2") (pintype "unspecified"))
    )
    (net (code "27") (name "Net-(R47-Pad1)") (class "Default")
      (node (ref "R47") (pin "1") (pinfunction "1_1") (pintype "unspecified"))
      (node (ref "U48") (pin "1") (pinfunction "1_1") (pintype "unspecified"))
    )
    (net (code "28") (name "Net-(U47-G)") (class "Default")
      (node (ref "U47") (pin "3") (pinfunction "G_3") (pintype "unspecified"))
      (node (ref "U48") (pin "4") (pinfunction "E_4") (pintype "unspecified"))
    )
    (net (code "29") (name "Net-(U48-BASE)") (class "Default")
      (node (ref "R413") (pin "1") (pinfunction "1_1") (pintype "unspecified"))
      (node (ref "U48") (pin "6") (pinfunction "BASE_6") (pintype "unspecified"))
    )
    (net (code "30") (name "PWM") (class "Default")
      (node (ref "E31") (pin "8") (pinfunction "GPIO33_8") (pintype "unspecified"))
      (node (ref "R47") (pin "2") (pinfunction "2_2") (pintype "unspecified"))
    )
    (net (code "31") (name "SCL") (class "Default")
      (node (ref "E31") (pin "36") (pinfunction "GPIO22/SCL_36") (pintype "unspecified"))
      (node (ref "J32") (pin "3") (pinfunction "3_3") (pintype "unspecified"))
      (node (ref "P21") (pin "3") (pinfunction "SCL_3") (pintype "bidirectional"))
      (node (ref "P23") (pin "3") (pinfunction "SCL_3") (pintype "bidirectional"))
      (node (ref "R36") (pin "1") (pinfunction "1_1") (pintype "unspecified"))
    )
    (net (code "32") (name "SDA") (class "Default")
      (node (ref "E31") (pin "33") (pinfunction "GPIO21/SDA_33") (pintype "unspecified"))
      (node (ref "J32") (pin "2") (pinfunction "2_2") (pintype "unspecified"))
      (node (ref "P21") (pin "4") (pinfunction "SDA_4") (pintype "bidirectional"))
      (node (ref "P23") (pin "4") (pinfunction "SDA_4") (pintype "bidirectional"))
      (node (ref "R35") (pin "1") (pinfunction "1_1") (pintype "unspecified"))
    )
    (net (code "33") (name "TICSIGNAL") (class "Default")
      (node (ref "E31") (pin "34") (pinfunction "RX_34") (pintype "unspecified"))
      (node (ref "Q11") (pin "1") (pinfunction "D_1") (pintype "unspecified"))
      (node (ref "R14") (pin "1") (pinfunction "1_1") (pintype "unspecified"))
    )
    (net (code "34") (name "VCC") (class "Default")
      (node (ref "LED11") (pin "1") (pinfunction "1_1") (pintype "unspecified"))
      (node (ref "P21") (pin "1") (pinfunction "VDD_1") (pintype "output"))
      (node (ref "P21") (pin "5") (pinfunction "ADDR_5") (pintype "passive"))
      (node (ref "P23") (pin "1") (pinfunction "VDD_1") (pintype "output"))
      (node (ref "R14") (pin "2") (pinfunction "2_2") (pintype "unspecified"))
    )
    (net (code "35") (name "ZC") (class "Default")
      (node (ref "E31") (pin "5") (pinfunction "GPIO34_5") (pintype "unspecified"))
      (node (ref "R42") (pin "1") (pinfunction "1_1") (pintype "unspecified"))
      (node (ref "U46") (pin "4") (pinfunction "COL_4") (pintype "unspecified"))
    )
    (net (code "36") (name "load") (class "Default")
      (node (ref "CN1") (pin "3") (pinfunction "3_3") (pintype "unspecified"))
      (node (ref "U47") (pin "1") (pinfunction "A1_1") (pintype "unspecified"))
    )
    (net (code "37") (name "neutre") (class "Default")
      (node (ref "A1") (pin "1") (pinfunction "L_1") (pintype "unspecified"))
      (node (ref "CN1") (pin "2") (pinfunction "2_2") (pintype "unspecified"))
      (node (ref "D1") (pin "2") (pinfunction "A_2") (pintype "unspecified"))
      (node (ref "D3") (pin "1") (pinfunction "K_1") (pintype "unspecified"))
      (node (ref "U31") (pin "4") (pinfunction "UN_4") (pintype "unspecified"))
    )
    (net (code "38") (name "phase") (class "Default")
      (node (ref "A1") (pin "2") (pinfunction "N_2") (pintype "unspecified"))
      (node (ref "CN1") (pin "1") (pinfunction "1_1") (pintype "unspecified"))
      (node (ref "R410") (pin "2") (pinfunction "2_2") (pintype "unspecified"))
      (node (ref "R413") (pin "2") (pinfunction "2_2") (pintype "unspecified"))
      (node (ref "R48") (pin "2") (pinfunction "2_2") (pintype "unspecified"))
      (node (ref "U31") (pin "1") (pinfunction "UL_1") (pintype "unspecified"))
      (node (ref "U47") (pin "2") (pinfunction "A2_2") (pintype "unspecified"))
    )
    (net (code "39") (name "unconnected-(E31-3V3-Pad1)") (class "Default")
      (node (ref "E31") (pin "1") (pinfunction "3V3_1") (pintype "unspecified"))
    )
    (net (code "40") (name "unconnected-(E31-GND-Pad14)") (class "Default")
      (node (ref "E31") (pin "14") (pinfunction "GND_14") (pintype "unspecified"))
    )
    (net (code "41") (name "unconnected-(E31-GPIO0-Pad25)") (class "Default")
      (node (ref "E31") (pin "25") (pinfunction "GPIO0_25") (pintype "unspecified"))
    )
    (net (code "42") (name "unconnected-(E31-GPIO2-Pad24)") (class "Default")
      (node (ref "E31") (pin "24") (pinfunction "GPIO2_24") (pintype "unspecified"))
    )
    (net (code "43") (name "unconnected-(E31-GPIO4-Pad26)") (class "Default")
      (node (ref "E31") (pin "26") (pinfunction "GPIO4_26") (pintype "unspecified"))
    )
    (net (code "44") (name "unconnected-(E31-GPIO5-Pad29)") (class "Default")
      (node (ref "E31") (pin "29") (pinfunction "GPIO5_29") (pintype "unspecified"))
    )
    (net (code "45") (name "unconnected-(E31-GPIO6-Pad20)") (class "Default")
      (node (ref "E31") (pin "20") (pinfunction "GPIO6_20") (pintype "unspecified"))
    )
    (net (code "46") (name "unconnected-(E31-GPIO7-Pad21)") (class "Default")
      (node (ref "E31") (pin "21") (pinfunction "GPIO7_21") (pintype "unspecified"))
    )
    (net (code "47") (name "unconnected-(E31-GPIO8-Pad22)") (class "Default")
      (node (ref "E31") (pin "22") (pinfunction "GPIO8_22") (pintype "unspecified"))
    )
    (net (code "48") (name "unconnected-(E31-GPIO9-Pad16)") (class "Default")
      (node (ref "E31") (pin "16") (pinfunction "GPIO9_16") (pintype "unspecified"))
    )
    (net (code "49") (name "unconnected-(E31-GPIO10-Pad17)") (class "Default")
      (node (ref "E31") (pin "17") (pinfunction "GPIO10_17") (pintype "unspecified"))
    )
    (net (code "50") (name "unconnected-(E31-GPIO11-Pad18)") (class "Default")
      (node (ref "E31") (pin "18") (pinfunction "GPIO11_18") (pintype "unspecified"))
    )
    (net (code "51") (name "unconnected-(E31-GPIO12-Pad13)") (class "Default")
      (node (ref "E31") (pin "13") (pinfunction "GPIO12_13") (pintype "unspecified"))
    )
    (net (code "52") (name "unconnected-(E31-GPIO13-Pad15)") (class "Default")
      (node (ref "E31") (pin "15") (pinfunction "GPIO13_15") (pintype "unspecified"))
    )
    (net (code "53") (name "unconnected-(E31-GPIO15-Pad23)") (class "Default")
      (node (ref "E31") (pin "23") (pinfunction "GPIO15_23") (pintype "unspecified"))
    )
    (net (code "54") (name "unconnected-(E31-GPIO18-Pad30)") (class "Default")
      (node (ref "E31") (pin "30") (pinfunction "GPIO18_30") (pintype "unspecified"))
    )
    (net (code "55") (name "unconnected-(E31-GPIO19-Pad31)") (class "Default")
      (node (ref "E31") (pin "31") (pinfunction "GPIO19_31") (pintype "unspecified"))
    )
    (net (code "56") (name "unconnected-(E31-GPIO23-Pad37)") (class "Default")
      (node (ref "E31") (pin "37") (pinfunction "GPIO23_37") (pintype "unspecified"))
    )
    (net (code "57") (name "unconnected-(E31-GPIO26-Pad10)") (class "Default")
      (node (ref "E31") (pin "10") (pinfunction "GPIO26_10") (pintype "unspecified"))
    )
    (net (code "58") (name "unconnected-(E31-GPIO35-Pad6)") (class "Default")
      (node (ref "E31") (pin "6") (pinfunction "GPIO35_6") (pintype "unspecified"))
    )
    (net (code "59") (name "unconnected-(E31-GPIO36-Pad3)") (class "Default")
      (node (ref "E31") (pin "3") (pinfunction "GPIO36_3") (pintype "unspecified"))
    )
    (net (code "60") (name "unconnected-(E31-GPIO39-Pad4)") (class "Default")
      (node (ref "E31") (pin "4") (pinfunction "GPIO39_4") (pintype "unspecified"))
    )
    (net (code "61") (name "unconnected-(E31-Pad2)") (class "Default")
      (node (ref "E31") (pin "2") (pinfunction "2_2") (pintype "unspecified"))
    )
    (net (code "62") (name "unconnected-(E31-TX-Pad35)") (class "Default")
      (node (ref "E31") (pin "35") (pinfunction "TX_35") (pintype "unspecified"))
    )
    (net (code "63") (name "unconnected-(J21-SLV-Pad2)") (class "Default")
      (node (ref "J21") (pin "2") (pinfunction "SLV_2") (pintype "unspecified"))
    )
    (net (code "64") (name "unconnected-(J21-SLV_S-Pad10)") (class "Default")
      (node (ref "J21") (pin "10") (pinfunction "SLV_S_10") (pintype "unspecified"))
    )
    (net (code "65") (name "unconnected-(J22-SLV-Pad2)") (class "Default")
      (node (ref "J22") (pin "2") (pinfunction "SLV_2") (pintype "unspecified"))
    )
    (net (code "66") (name "unconnected-(J22-SLV_S-Pad10)") (class "Default")
      (node (ref "J22") (pin "10") (pinfunction "SLV_S_10") (pintype "unspecified"))
    )
    (net (code "67") (name "unconnected-(J23-SLV-Pad2)") (class "Default")
      (node (ref "J23") (pin "2") (pinfunction "SLV_2") (pintype "unspecified"))
    )
    (net (code "68") (name "unconnected-(J23-SLV_S-Pad10)") (class "Default")
      (node (ref "J23") (pin "10") (pinfunction "SLV_S_10") (pintype "unspecified"))
    )
    (net (code "69") (name "unconnected-(J24-SLV-Pad2)") (class "Default")
      (node (ref "J24") (pin "2") (pinfunction "SLV_2") (pintype "unspecified"))
    )
    (net (code "70") (name "unconnected-(J24-SLV_S-Pad10)") (class "Default")
      (node (ref "J24") (pin "10") (pinfunction "SLV_S_10") (pintype "unspecified"))
    )
    (net (code "71") (name "unconnected-(P21-ALRT-Pad6)") (class "Default")
      (node (ref "P21") (pin "6") (pinfunction "ALRT_6") (pintype "passive"))
    )
    (net (code "72") (name "unconnected-(P23-ALRT-Pad6)") (class "Default")
      (node (ref "P23") (pin "6") (pinfunction "ALRT_6") (pintype "passive"))
    )
    (net (code "73") (name "unconnected-(U31-GND-Pad2)") (class "Default")
      (node (ref "U31") (pin "2") (pinfunction "GND_2") (pintype "unspecified"))
    )
    (net (code "74") (name "unconnected-(U31-GND-Pad3)") (class "Default")
      (node (ref "U31") (pin "3") (pinfunction "GND_3") (pintype "unspecified"))
    )
    (net (code "75") (name "unconnected-(U31-PF-Pad8)") (class "Default")
      (node (ref "U31") (pin "8") (pinfunction "PF_8") (pintype "unspecified"))
    )
    (net (code "76") (name "unconnected-(U48-NC-Pad3)") (class "Default")
      (node (ref "U48") (pin "3") (pinfunction "NC_3") (pintype "unspecified"))
    )
    (net (code "77") (name "unconnected-(U48-NC-Pad5)") (class "Default")
      (node (ref "U48") (pin "5") (pinfunction "NC_5") (pintype "unspecified"))
    )
  )
)
